# Sch_Quick_Dev_R2.net
KiCad netlist of a schematic drawn in EasyEDA
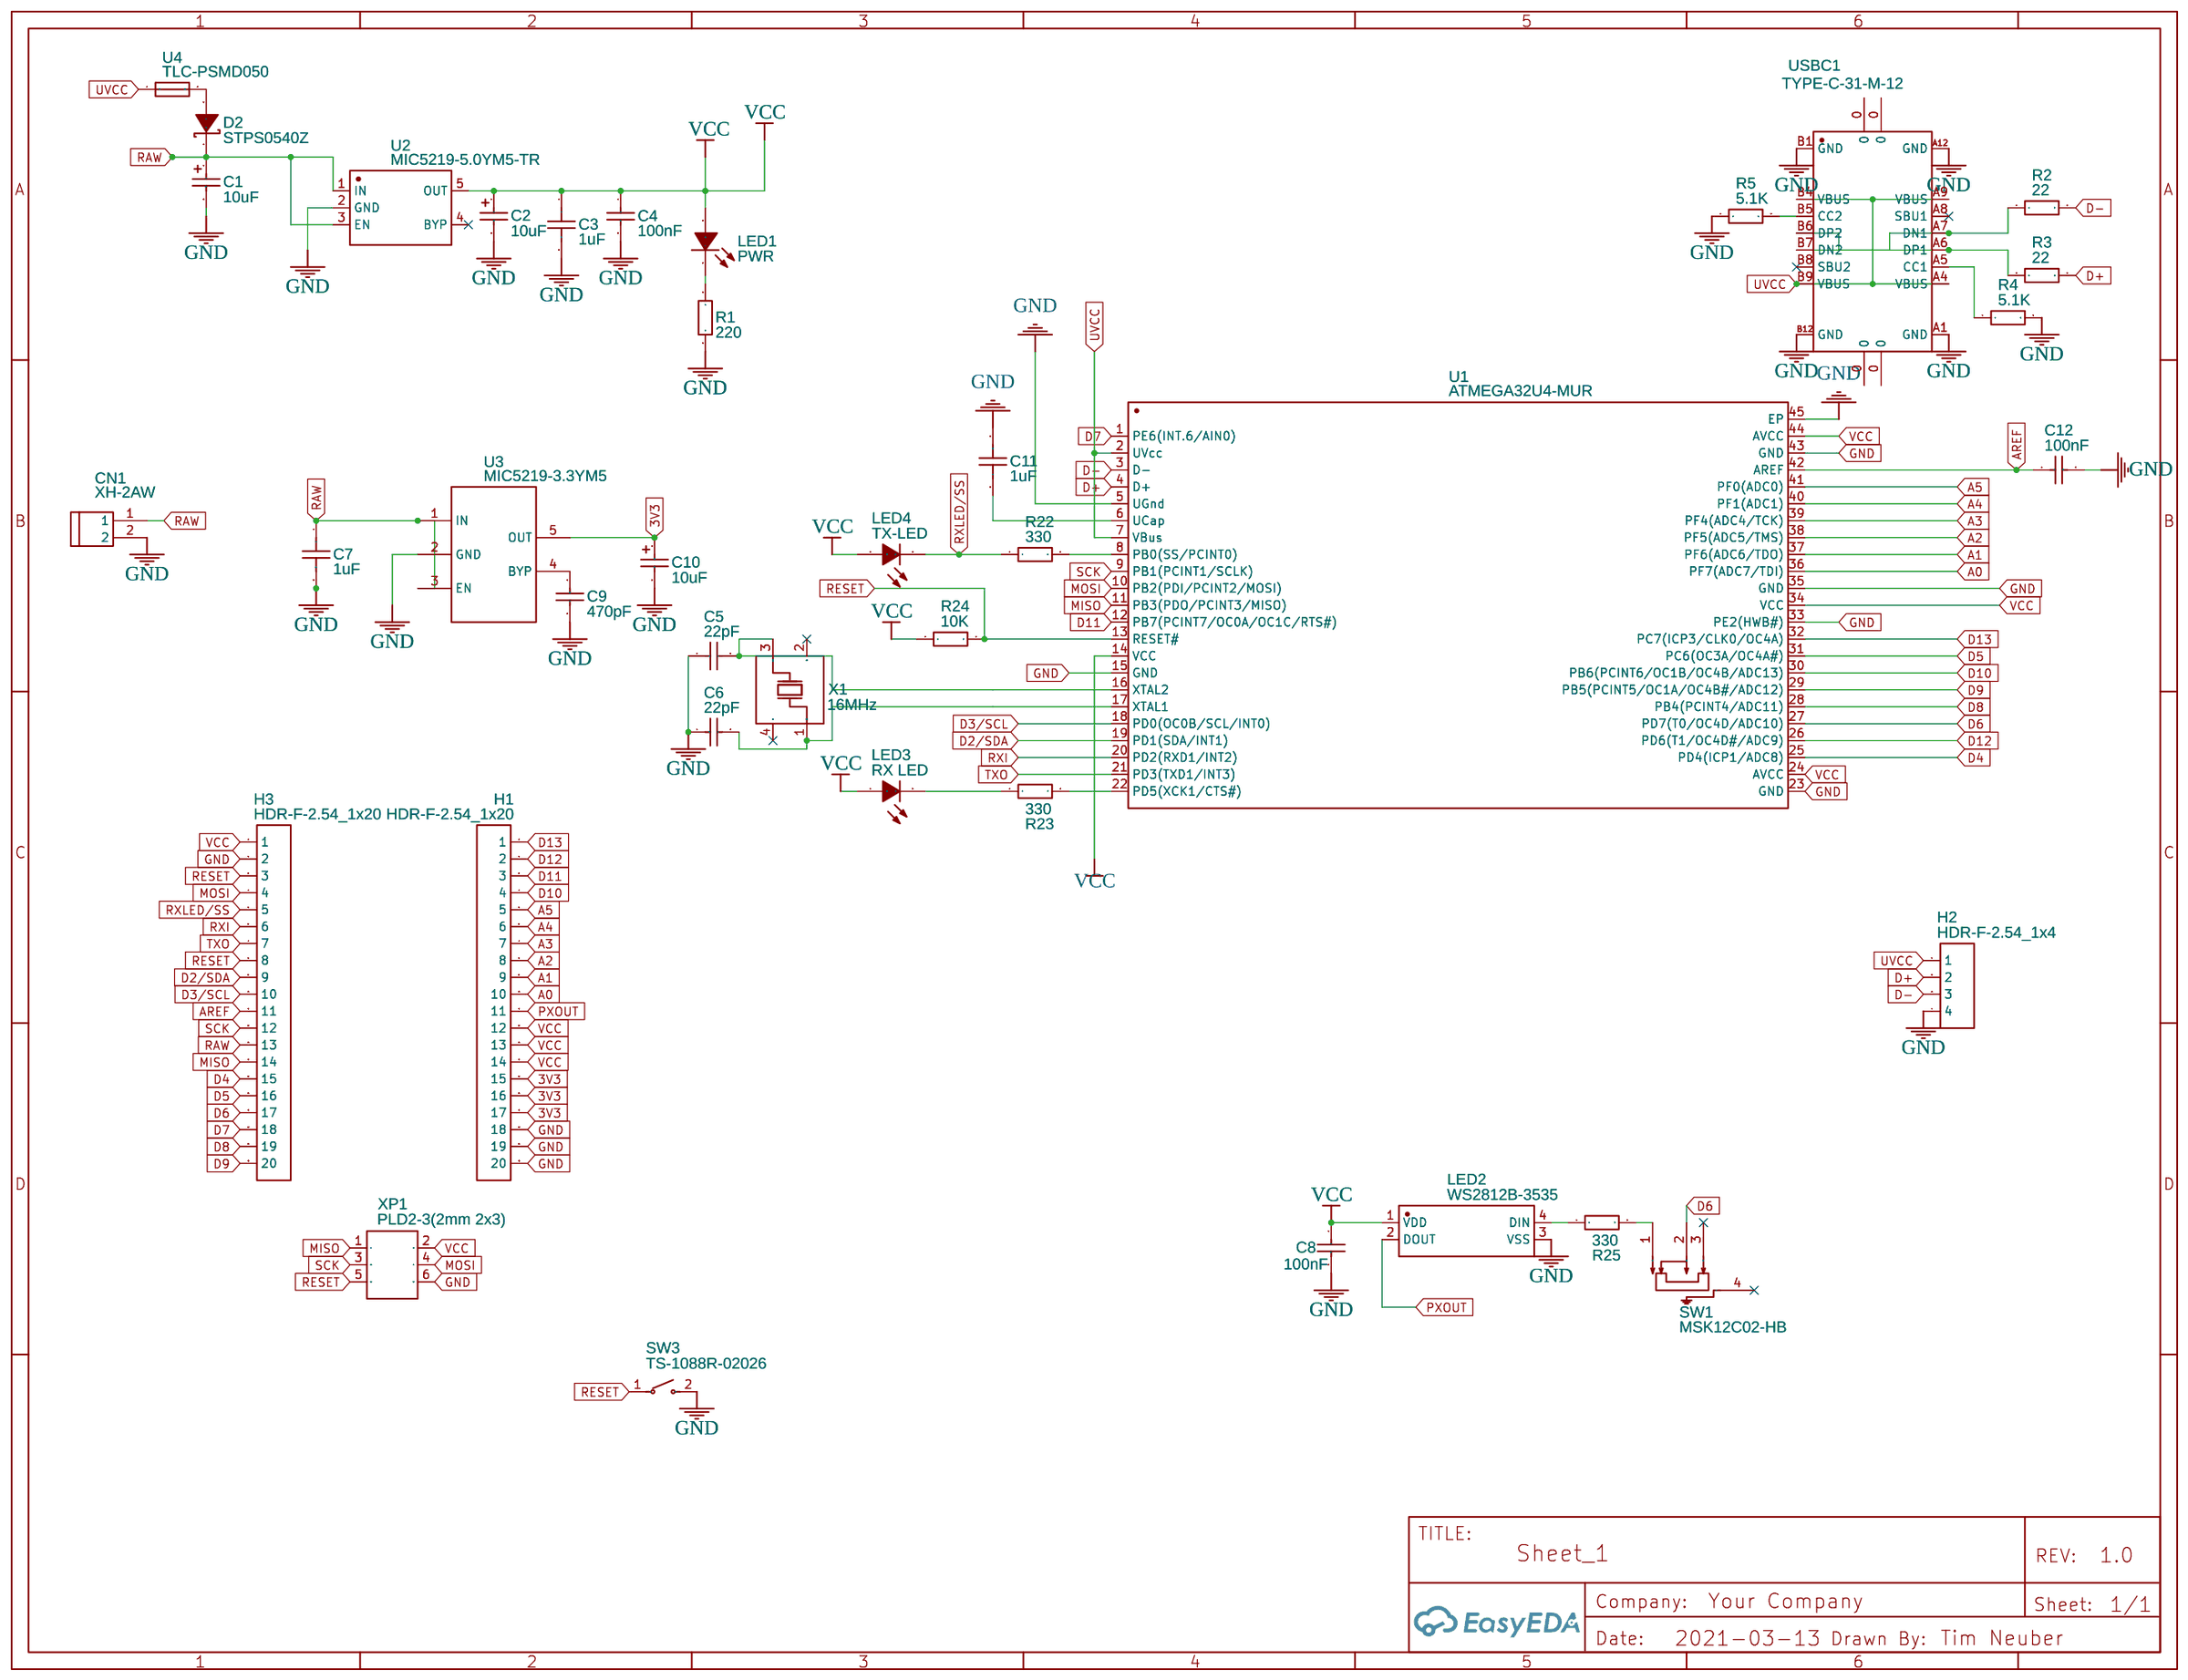
[diagram p0: schematic sheet]

(export (version "E")
  (design (tool "Eeschema 10.0.6"))
  (components
    (comp (ref "C1")
      (value "10uF")
      (fields
        (field (name "BOM_Manufacturer Part") "TAJA106K016RNJ")
        (field (name "BOM_Supplier Part") "C7171")
      )
      (libsource (lib "") (part "TAJA106K016RNJ"))
    )
    (comp (ref "C2")
      (value "10uF")
      (fields
        (field (name "BOM_Manufacturer Part") "TAJA106K016RNJ")
        (field (name "BOM_Supplier Part") "C7171")
      )
      (libsource (lib "") (part "TAJA106K016RNJ"))
    )
    (comp (ref "C3")
      (value "1uF")
      (fields
        (field (name "BOM_Manufacturer Part") "CL05A105KA5NQNC")
        (field (name "BOM_Supplier Part") "C52923")
      )
      (libsource (lib "") (part "CL05A105KA5NQNC"))
    )
    (comp (ref "C4")
      (value "100nF")
      (fields
        (field (name "BOM_Manufacturer Part") "CL05B104KO5NNNC")
        (field (name "BOM_Supplier Part") "C1525")
      )
      (libsource (lib "") (part "CL05B104KO5NNNC"))
    )
    (comp (ref "C5")
      (value "22pF")
      (fields
        (field (name "BOM_Manufacturer Part") "0402CG220J500NT")
        (field (name "BOM_Supplier Part") "C1555")
      )
      (libsource (lib "") (part "0402CG220J500NT"))
    )
    (comp (ref "C6")
      (value "22pF")
      (fields
        (field (name "BOM_Manufacturer Part") "0402CG220J500NT")
        (field (name "BOM_Supplier Part") "C1555")
      )
      (libsource (lib "") (part "0402CG220J500NT"))
    )
    (comp (ref "C7")
      (value "1uF")
      (fields
        (field (name "BOM_Manufacturer Part") "CL05A105KA5NQNC")
        (field (name "BOM_Supplier Part") "C52923")
      )
      (libsource (lib "") (part "CL05A105KA5NQNC"))
    )
    (comp (ref "C8")
      (value "100nF")
      (fields
        (field (name "BOM_Manufacturer Part") "CL05B104KO5NNNC")
        (field (name "BOM_Supplier Part") "C1525")
      )
      (libsource (lib "") (part "CL05B104KO5NNNC"))
    )
    (comp (ref "C9")
      (value "470pF")
      (fields
        (field (name "BOM_Manufacturer Part") "0402B471K500NT")
        (field (name "BOM_Supplier Part") "C1537")
      )
      (libsource (lib "") (part "0402B471K500NT"))
    )
    (comp (ref "C10")
      (value "10uF")
      (fields
        (field (name "BOM_Manufacturer Part") "TAJA106K016RNJ")
        (field (name "BOM_Supplier Part") "C7171")
      )
      (libsource (lib "") (part "TAJA106K016RNJ"))
    )
    (comp (ref "C11")
      (value "1uF")
      (fields
        (field (name "BOM_Manufacturer Part") "CL05A105KA5NQNC")
        (field (name "BOM_Supplier Part") "C52923")
      )
      (libsource (lib "") (part "CL05A105KA5NQNC"))
    )
    (comp (ref "C12")
      (value "100nF")
      (fields
        (field (name "BOM_Manufacturer Part") "CL05B104KO5NNNC")
        (field (name "BOM_Supplier Part") "C1525")
      )
      (libsource (lib "") (part "CL05B104KO5NNNC_1"))
    )
    (comp (ref "CN1")
      (value "XH-2AW")
      (fields (field (name "BOM_Supplier Part") "C33132"))
      (libsource (lib "") (part "XH-2AW"))
    )
    (comp (ref "D2")
      (value "STPS0540Z")
      (fields (field (name "BOM_Supplier Part") "C181835"))
      (libsource (lib "") (part "STPS0540Z"))
    )
    (comp (ref "H1")
      (value "HDR-F-2.54_1x20")
      (fields (field (name "BOM_Supplier Part") "C50984"))
      (libsource (lib "") (part "HDR-F-2.54_1x20_1"))
    )
    (comp (ref "H2")
      (value "HDR-F-2.54_1x4")
      (fields (field (name "BOM_Supplier Part") "C225501"))
      (libsource (lib "") (part "HDR-F-2.54_1x4"))
    )
    (comp (ref "H3")
      (value "HDR-F-2.54_1x20")
      (fields (field (name "BOM_Supplier Part") "C50984"))
      (libsource (lib "") (part "HDR-F-2.54_1x20"))
    )
    (comp (ref "LED1")
      (value "PWR")
      (fields (field (name "BOM_Manufacturer Part") "KT-0603R") (field (name "BOM_Supplier Part") "C2286"))
      (libsource (lib "") (part "KT-0603R"))
    )
    (comp (ref "LED2")
      (value "WS2812B-3535")
      (fields (field (name "BOM_Supplier Part") "C114583"))
      (libsource (lib "") (part "WS2812B-3535"))
    )
    (comp (ref "LED3")
      (value "RX LED")
      (fields
        (field (name "BOM_Manufacturer Part") "19-217/BHC-ZL1M2RY/3T")
        (field (name "BOM_Supplier Part") "C72041")
      )
      (libsource (lib "") (part "19-217/BHC-ZL1M2RY/3T"))
    )
    (comp (ref "LED4")
      (value "TX-LED")
      (fields
        (field (name "BOM_Manufacturer Part") "19-217/BHC-ZL1M2RY/3T")
        (field (name "BOM_Supplier Part") "C72041")
      )
      (libsource (lib "") (part "19-217/BHC-ZL1M2RY/3T"))
    )
    (comp (ref "R1")
      (value "220")
      (fields
        (field (name "BOM_Manufacturer Part") "0603WAF2200T5E")
        (field (name "BOM_Supplier Part") "C22962")
      )
      (libsource (lib "") (part "0603WAF2200T5E"))
    )
    (comp (ref "R2")
      (value "22")
      (fields
        (field (name "BOM_Manufacturer Part") "0402WGF220JTCE")
        (field (name "BOM_Supplier Part") "C25092")
      )
      (libsource (lib "") (part "0402WGF220JTCE"))
    )
    (comp (ref "R3")
      (value "22")
      (fields
        (field (name "BOM_Manufacturer Part") "0402WGF220JTCE")
        (field (name "BOM_Supplier Part") "C25092")
      )
      (libsource (lib "") (part "0402WGF220JTCE"))
    )
    (comp (ref "R4")
      (value "5.1K")
      (fields
        (field (name "BOM_Manufacturer Part") "0402WGF5101TCE")
        (field (name "BOM_Supplier Part") "C25905")
      )
      (libsource (lib "") (part "0402WGF5101TCE"))
    )
    (comp (ref "R5")
      (value "5.1K")
      (fields
        (field (name "BOM_Manufacturer Part") "0402WGF5101TCE")
        (field (name "BOM_Supplier Part") "C25905")
      )
      (libsource (lib "") (part "0402WGF5101TCE"))
    )
    (comp (ref "R22")
      (value "330")
      (fields
        (field (name "BOM_Manufacturer Part") "0402WGF3300TCE")
        (field (name "BOM_Supplier Part") "C25104")
      )
      (libsource (lib "") (part "0402WGF3300TCE"))
    )
    (comp (ref "R23")
      (value "330")
      (fields
        (field (name "BOM_Manufacturer Part") "0402WGF3300TCE")
        (field (name "BOM_Supplier Part") "C25104")
      )
      (libsource (lib "") (part "0402WGF3300TCE"))
    )
    (comp (ref "R24")
      (value "10K")
      (fields
        (field (name "BOM_Manufacturer Part") "0402WGF1002TCE")
        (field (name "BOM_Supplier Part") "C25744")
      )
      (libsource (lib "") (part "0402WGF1002TCE"))
    )
    (comp (ref "R25")
      (value "330")
      (fields
        (field (name "BOM_Manufacturer Part") "0402WGF3300TCE")
        (field (name "BOM_Supplier Part") "C25104")
      )
      (libsource (lib "") (part "0402WGF3300TCE"))
    )
    (comp (ref "SW1")
      (value "MSK12C02-HB")
      (fields (field (name "BOM_Supplier Part") "C431541"))
      (libsource (lib "") (part "MSK12C02-HB"))
    )
    (comp (ref "SW3")
      (value "TS-1088R-02026")
      (fields (field (name "BOM_Supplier Part") "C455280"))
      (libsource (lib "") (part "TS-1088R-02026"))
    )
    (comp (ref "U1")
      (value "ATMEGA32U4-MUR")
      (fields (field (name "BOM_Supplier Part") "C45874"))
      (libsource (lib "") (part "ATMEGA32U4-MUR"))
    )
    (comp (ref "U2")
      (value "MIC5219-5.0YM5-TR")
      (fields (field (name "BOM_Supplier Part") "C144182"))
      (libsource (lib "") (part "MIC5219-5.0YM5-TR"))
    )
    (comp (ref "U3")
      (value "MIC5219-3.3YM5")
      (fields (field (name "BOM_Supplier Part") "C29613"))
      (libsource (lib "") (part "MIC5219-3.3YM5"))
    )
    (comp (ref "U4")
      (value "TLC-PSMD050")
      (fields (field (name "BOM_Supplier Part") "C261942"))
      (libsource (lib "") (part "TLC-PSMD050"))
    )
    (comp (ref "USBC1")
      (value "TYPE-C-31-M-12")
      (fields (field (name "BOM_Supplier Part") "C165948"))
      (libsource (lib "") (part "TYPE-C-31-M-12"))
    )
    (comp (ref "X1")
      (value "16MHz")
      (fields
        (field (name "BOM_Manufacturer Part") "X322516MLB4SI")
        (field (name "BOM_Supplier Part") "C13738")
      )
      (libsource (lib "") (part "X322516MLB4SI"))
    )
    (comp (ref "XP1")
      (value "PLD2-3(2mm 2x3)")
      (fields (field (name "BOM_Manufacturer Part") "PLD-3 2,54 2x3"))
      (libsource (lib "") (part "PLD2-3(2mm 2x3)"))
    )
  )
  (nets
    (net (code "1") (name "3V3") (class "Default")
      (node (ref "C10") (pin "1") (pinfunction "1_1") (pintype "input"))
      (node (ref "H1") (pin "15") (pinfunction "15_15") (pintype "unspecified"))
      (node (ref "H1") (pin "16") (pinfunction "16_16") (pintype "unspecified"))
      (node (ref "H1") (pin "17") (pinfunction "17_17") (pintype "unspecified"))
      (node (ref "U3") (pin "5") (pinfunction "OUT_5") (pintype "unspecified"))
    )
    (net (code "2") (name "A0") (class "Default")
      (node (ref "H1") (pin "10") (pinfunction "10_10") (pintype "unspecified"))
      (node (ref "U1") (pin "36") (pinfunction "PF7(ADC7/TDI)_36") (pintype "unspecified"))
    )
    (net (code "3") (name "A1") (class "Default")
      (node (ref "H1") (pin "9") (pinfunction "9_9") (pintype "unspecified"))
      (node (ref "U1") (pin "37") (pinfunction "PF6(ADC6/TDO)_37") (pintype "unspecified"))
    )
    (net (code "4") (name "A2") (class "Default")
      (node (ref "H1") (pin "8") (pinfunction "8_8") (pintype "unspecified"))
      (node (ref "U1") (pin "38") (pinfunction "PF5(ADC5/TMS)_38") (pintype "unspecified"))
    )
    (net (code "5") (name "A3") (class "Default")
      (node (ref "H1") (pin "7") (pinfunction "7_7") (pintype "unspecified"))
      (node (ref "U1") (pin "39") (pinfunction "PF4(ADC4/TCK)_39") (pintype "unspecified"))
    )
    (net (code "6") (name "A4") (class "Default")
      (node (ref "H1") (pin "6") (pinfunction "6_6") (pintype "unspecified"))
      (node (ref "U1") (pin "40") (pinfunction "PF1(ADC1)_40") (pintype "unspecified"))
    )
    (net (code "7") (name "A5") (class "Default")
      (node (ref "H1") (pin "5") (pinfunction "5_5") (pintype "unspecified"))
      (node (ref "U1") (pin "41") (pinfunction "PF0(ADC0)_41") (pintype "unspecified"))
    )
    (net (code "8") (name "AREF") (class "Default")
      (node (ref "C12") (pin "1") (pinfunction "1_1") (pintype "input"))
      (node (ref "H3") (pin "11") (pinfunction "11_11") (pintype "unspecified"))
      (node (ref "U1") (pin "42") (pinfunction "AREF_42") (pintype "unspecified"))
    )
    (net (code "9") (name "D+") (class "Default")
      (node (ref "H2") (pin "2") (pinfunction "2_2") (pintype "unspecified"))
      (node (ref "R3") (pin "2") (pinfunction "2_2") (pintype "input"))
      (node (ref "U1") (pin "4") (pinfunction "D+_4") (pintype "unspecified"))
    )
    (net (code "10") (name "D-") (class "Default")
      (node (ref "H2") (pin "3") (pinfunction "3_3") (pintype "unspecified"))
      (node (ref "R2") (pin "2") (pinfunction "2_2") (pintype "input"))
      (node (ref "U1") (pin "3") (pinfunction "D-_3") (pintype "unspecified"))
    )
    (net (code "11") (name "D2{slash}SDA") (class "Default")
      (node (ref "H3") (pin "9") (pinfunction "9_9") (pintype "unspecified"))
      (node (ref "U1") (pin "19") (pinfunction "PD1(SDA/INT1)_19") (pintype "unspecified"))
    )
    (net (code "12") (name "D3{slash}SCL") (class "Default")
      (node (ref "H3") (pin "10") (pinfunction "10_10") (pintype "unspecified"))
      (node (ref "U1") (pin "18") (pinfunction "PD0(OC0B/SCL/INT0)_18") (pintype "unspecified"))
    )
    (net (code "13") (name "D4") (class "Default")
      (node (ref "H3") (pin "15") (pinfunction "15_15") (pintype "unspecified"))
      (node (ref "U1") (pin "25") (pinfunction "PD4(ICP1/ADC8)_25") (pintype "unspecified"))
    )
    (net (code "14") (name "D5") (class "Default")
      (node (ref "H3") (pin "16") (pinfunction "16_16") (pintype "unspecified"))
      (node (ref "U1") (pin "31") (pinfunction "PC6(OC3A/OC4A#)_31") (pintype "unspecified"))
    )
    (net (code "15") (name "D6") (class "Default")
      (node (ref "H3") (pin "17") (pinfunction "17_17") (pintype "unspecified"))
      (node (ref "SW1") (pin "2") (pinfunction "2_2") (pintype "unspecified"))
      (node (ref "U1") (pin "27") (pinfunction "PD7(T0/OC4D/ADC10)_27") (pintype "unspecified"))
    )
    (net (code "16") (name "D7") (class "Default")
      (node (ref "H3") (pin "18") (pinfunction "18_18") (pintype "unspecified"))
      (node (ref "U1") (pin "1") (pinfunction "PE6(INT.6/AIN0)_1") (pintype "unspecified"))
    )
    (net (code "17") (name "D8") (class "Default")
      (node (ref "H3") (pin "19") (pinfunction "19_19") (pintype "unspecified"))
      (node (ref "U1") (pin "28") (pinfunction "PB4(PCINT4/ADC11)_28") (pintype "unspecified"))
    )
    (net (code "18") (name "D9") (class "Default")
      (node (ref "H3") (pin "20") (pinfunction "20_20") (pintype "unspecified"))
      (node (ref "U1") (pin "29") (pinfunction "PB5(PCINT5/OC1A/OC4B#/ADC12)_29") (pintype "unspecified"))
    )
    (net (code "19") (name "D10") (class "Default")
      (node (ref "H1") (pin "4") (pinfunction "4_4") (pintype "unspecified"))
      (node (ref "U1") (pin "30") (pinfunction "PB6(PCINT6/OC1B/OC4B/ADC13)_30") (pintype "unspecified"))
    )
    (net (code "20") (name "D11") (class "Default")
      (node (ref "H1") (pin "3") (pinfunction "3_3") (pintype "unspecified"))
      (node (ref "U1") (pin "12") (pinfunction "PB7(PCINT7/OC0A/OC1C/RTS#)_12") (pintype "unspecified"))
    )
    (net (code "21") (name "D12") (class "Default")
      (node (ref "H1") (pin "2") (pinfunction "2_2") (pintype "unspecified"))
      (node (ref "U1") (pin "26") (pinfunction "PD6(T1/OC4D#/ADC9)_26") (pintype "unspecified"))
    )
    (net (code "22") (name "D13") (class "Default")
      (node (ref "H1") (pin "1") (pinfunction "1_1") (pintype "unspecified"))
      (node (ref "U1") (pin "32") (pinfunction "PC7(ICP3/CLK0/OC4A)_32") (pintype "unspecified"))
    )
    (net (code "23") (name "GND") (class "Default")
      (node (ref "C1") (pin "2") (pinfunction "2_2") (pintype "input"))
      (node (ref "C10") (pin "2") (pinfunction "2_2") (pintype "input"))
      (node (ref "C11") (pin "1") (pinfunction "1_1") (pintype "unspecified"))
      (node (ref "C12") (pin "2") (pinfunction "2_2") (pintype "input"))
      (node (ref "C2") (pin "2") (pinfunction "2_2") (pintype "input"))
      (node (ref "C3") (pin "2") (pinfunction "2_2") (pintype "unspecified"))
      (node (ref "C4") (pin "2") (pinfunction "2_2") (pintype "input"))
      (node (ref "C5") (pin "1") (pinfunction "1_1") (pintype "input"))
      (node (ref "C6") (pin "1") (pinfunction "1_1") (pintype "input"))
      (node (ref "C7") (pin "2") (pinfunction "2_2") (pintype "unspecified"))
      (node (ref "C8") (pin "2") (pinfunction "2_2") (pintype "input"))
      (node (ref "C9") (pin "1") (pinfunction "1_1") (pintype "input"))
      (node (ref "CN1") (pin "2") (pinfunction "2_2") (pintype "unspecified"))
      (node (ref "H1") (pin "18") (pinfunction "18_18") (pintype "unspecified"))
      (node (ref "H1") (pin "19") (pinfunction "19_19") (pintype "unspecified"))
      (node (ref "H1") (pin "20") (pinfunction "20_20") (pintype "unspecified"))
      (node (ref "H2") (pin "4") (pinfunction "4_4") (pintype "unspecified"))
      (node (ref "H3") (pin "2") (pinfunction "2_2") (pintype "unspecified"))
      (node (ref "LED2") (pin "3") (pinfunction "VSS_3") (pintype "unspecified"))
      (node (ref "R1") (pin "1") (pinfunction "1_1") (pintype "input"))
      (node (ref "R4") (pin "2") (pinfunction "2_2") (pintype "input"))
      (node (ref "R5") (pin "1") (pinfunction "1_1") (pintype "input"))
      (node (ref "SW3") (pin "2") (pinfunction "2_2") (pintype "unspecified"))
      (node (ref "U1") (pin "15") (pinfunction "GND_15") (pintype "unspecified"))
      (node (ref "U1") (pin "23") (pinfunction "GND_23") (pintype "unspecified"))
      (node (ref "U1") (pin "33") (pinfunction "PE2(HWB#)_33") (pintype "unspecified"))
      (node (ref "U1") (pin "35") (pinfunction "GND_35") (pintype "unspecified"))
      (node (ref "U1") (pin "43") (pinfunction "GND_43") (pintype "unspecified"))
      (node (ref "U1") (pin "45") (pinfunction "EP_45") (pintype "unspecified"))
      (node (ref "U1") (pin "5") (pinfunction "UGnd_5") (pintype "unspecified"))
      (node (ref "U2") (pin "2") (pinfunction "GND_2") (pintype "unspecified"))
      (node (ref "U3") (pin "2") (pinfunction "GND_2") (pintype "unspecified"))
      (node (ref "USBC1") (pin "A1") (pinfunction "GND_A1") (pintype "unspecified"))
      (node (ref "USBC1") (pin "A12") (pinfunction "GND_A12") (pintype "unspecified"))
      (node (ref "USBC1") (pin "B1") (pinfunction "GND_B1") (pintype "unspecified"))
      (node (ref "USBC1") (pin "B12") (pinfunction "GND_B12") (pintype "unspecified"))
      (node (ref "XP1") (pin "6") (pinfunction "6_6") (pintype "unspecified"))
    )
    (net (code "24") (name "MISO") (class "Default")
      (node (ref "H3") (pin "14") (pinfunction "14_14") (pintype "unspecified"))
      (node (ref "U1") (pin "11") (pinfunction "PB3(PDO/PCINT3/MISO)_11") (pintype "unspecified"))
      (node (ref "XP1") (pin "1") (pinfunction "1_1") (pintype "unspecified"))
    )
    (net (code "25") (name "MOSI") (class "Default")
      (node (ref "H3") (pin "4") (pinfunction "4_4") (pintype "unspecified"))
      (node (ref "U1") (pin "10") (pinfunction "PB2(PDI/PCINT2/MOSI)_10") (pintype "unspecified"))
      (node (ref "XP1") (pin "4") (pinfunction "4_4") (pintype "unspecified"))
    )
    (net (code "26") (name "Net-(D2-A)") (class "Default")
      (node (ref "D2") (pin "2") (pinfunction "A_2") (pintype "unspecified"))
      (node (ref "U4") (pin "2") (pinfunction "2_2") (pintype "unspecified"))
    )
    (net (code "27") (name "Net-(LED1-K)") (class "Default")
      (node (ref "LED1") (pin "2") (pinfunction "K_2") (pintype "unspecified"))
      (node (ref "R1") (pin "2") (pinfunction "2_2") (pintype "input"))
    )
    (net (code "28") (name "Net-(LED2-DIN)") (class "Default")
      (node (ref "LED2") (pin "4") (pinfunction "DIN_4") (pintype "unspecified"))
      (node (ref "R25") (pin "1") (pinfunction "1_1") (pintype "input"))
    )
    (net (code "29") (name "Net-(LED3-C)") (class "Default")
      (node (ref "LED3") (pin "2") (pinfunction "C_2") (pintype "input"))
      (node (ref "R23") (pin "1") (pinfunction "1_1") (pintype "input"))
    )
    (net (code "30") (name "Net-(R25-Pad2)") (class "Default")
      (node (ref "R25") (pin "2") (pinfunction "2_2") (pintype "input"))
      (node (ref "SW1") (pin "1") (pinfunction "1_1") (pintype "unspecified"))
    )
    (net (code "31") (name "Net-(U1-PB0(SS{slash}PCINT0))") (class "Default")
      (node (ref "R22") (pin "2") (pinfunction "2_2") (pintype "input"))
      (node (ref "U1") (pin "8") (pinfunction "PB0(SS/PCINT0)_8") (pintype "unspecified"))
    )
    (net (code "32") (name "Net-(U1-PD5(XCK1{slash}CTS#))") (class "Default")
      (node (ref "R23") (pin "2") (pinfunction "2_2") (pintype "input"))
      (node (ref "U1") (pin "22") (pinfunction "PD5(XCK1/CTS#)_22") (pintype "unspecified"))
    )
    (net (code "33") (name "Net-(U1-UCap)") (class "Default")
      (node (ref "C11") (pin "2") (pinfunction "2_2") (pintype "unspecified"))
      (node (ref "U1") (pin "6") (pinfunction "UCap_6") (pintype "unspecified"))
    )
    (net (code "34") (name "Net-(U1-XTAL1)") (class "Default")
      (node (ref "C6") (pin "2") (pinfunction "2_2") (pintype "input"))
      (node (ref "U1") (pin "17") (pinfunction "XTAL1_17") (pintype "unspecified"))
      (node (ref "X1") (pin "1") (pinfunction "OSC1_1") (pintype "unspecified"))
    )
    (net (code "35") (name "Net-(U1-XTAL2)") (class "Default")
      (node (ref "C5") (pin "2") (pinfunction "2_2") (pintype "input"))
      (node (ref "U1") (pin "16") (pinfunction "XTAL2_16") (pintype "unspecified"))
      (node (ref "X1") (pin "3") (pinfunction "OSC2_3") (pintype "unspecified"))
    )
    (net (code "36") (name "Net-(U3-BYP)") (class "Default")
      (node (ref "C9") (pin "2") (pinfunction "2_2") (pintype "input"))
      (node (ref "U3") (pin "4") (pinfunction "BYP_4") (pintype "unspecified"))
    )
    (net (code "37") (name "Net-(USBC1-CC1)") (class "Default")
      (node (ref "R4") (pin "1") (pinfunction "1_1") (pintype "input"))
      (node (ref "USBC1") (pin "A5") (pinfunction "CC1_A5") (pintype "unspecified"))
    )
    (net (code "38") (name "Net-(USBC1-CC2)") (class "Default")
      (node (ref "R5") (pin "2") (pinfunction "2_2") (pintype "input"))
      (node (ref "USBC1") (pin "B5") (pinfunction "CC2_B5") (pintype "unspecified"))
    )
    (net (code "39") (name "Net-(USBC1-DN1)") (class "Default")
      (node (ref "R2") (pin "1") (pinfunction "1_1") (pintype "input"))
      (node (ref "USBC1") (pin "A7") (pinfunction "DN1_A7") (pintype "unspecified"))
      (node (ref "USBC1") (pin "B7") (pinfunction "DN2_B7") (pintype "unspecified"))
    )
    (net (code "40") (name "Net-(USBC1-DP1)") (class "Default")
      (node (ref "R3") (pin "1") (pinfunction "1_1") (pintype "input"))
      (node (ref "USBC1") (pin "A6") (pinfunction "DP1_A6") (pintype "unspecified"))
      (node (ref "USBC1") (pin "B6") (pinfunction "DP2_B6") (pintype "unspecified"))
    )
    (net (code "41") (name "PXOUT") (class "Default")
      (node (ref "H1") (pin "11") (pinfunction "11_11") (pintype "unspecified"))
      (node (ref "LED2") (pin "2") (pinfunction "DOUT_2") (pintype "unspecified"))
    )
    (net (code "42") (name "RAW") (class "Default")
      (node (ref "C1") (pin "1") (pinfunction "1_1") (pintype "input"))
      (node (ref "C7") (pin "1") (pinfunction "1_1") (pintype "unspecified"))
      (node (ref "CN1") (pin "1") (pinfunction "1_1") (pintype "unspecified"))
      (node (ref "D2") (pin "1") (pinfunction "K_1") (pintype "unspecified"))
      (node (ref "H3") (pin "13") (pinfunction "13_13") (pintype "unspecified"))
      (node (ref "U2") (pin "1") (pinfunction "IN_1") (pintype "unspecified"))
      (node (ref "U2") (pin "3") (pinfunction "EN_3") (pintype "unspecified"))
      (node (ref "U3") (pin "1") (pinfunction "IN_1") (pintype "unspecified"))
      (node (ref "U3") (pin "3") (pinfunction "EN_3") (pintype "unspecified"))
    )
    (net (code "43") (name "RESET") (class "Default")
      (node (ref "H3") (pin "3") (pinfunction "3_3") (pintype "unspecified"))
      (node (ref "H3") (pin "8") (pinfunction "8_8") (pintype "unspecified"))
      (node (ref "R24") (pin "2") (pinfunction "2_2") (pintype "input"))
      (node (ref "SW3") (pin "1") (pinfunction "1_1") (pintype "unspecified"))
      (node (ref "U1") (pin "13") (pinfunction "RESET#_13") (pintype "unspecified"))
      (node (ref "XP1") (pin "5") (pinfunction "5_5") (pintype "unspecified"))
    )
    (net (code "44") (name "RXI") (class "Default")
      (node (ref "H3") (pin "6") (pinfunction "6_6") (pintype "unspecified"))
      (node (ref "U1") (pin "20") (pinfunction "PD2(RXD1/INT2)_20") (pintype "unspecified"))
    )
    (net (code "45") (name "RXLED{slash}SS") (class "Default")
      (node (ref "H3") (pin "5") (pinfunction "5_5") (pintype "unspecified"))
      (node (ref "LED4") (pin "2") (pinfunction "C_2") (pintype "input"))
      (node (ref "R22") (pin "1") (pinfunction "1_1") (pintype "input"))
    )
    (net (code "46") (name "SCK") (class "Default")
      (node (ref "H3") (pin "12") (pinfunction "12_12") (pintype "unspecified"))
      (node (ref "U1") (pin "9") (pinfunction "PB1(PCINT1/SCLK)_9") (pintype "unspecified"))
      (node (ref "XP1") (pin "3") (pinfunction "3_3") (pintype "unspecified"))
    )
    (net (code "47") (name "TXO") (class "Default")
      (node (ref "H3") (pin "7") (pinfunction "7_7") (pintype "unspecified"))
      (node (ref "U1") (pin "21") (pinfunction "PD3(TXD1/INT3)_21") (pintype "unspecified"))
    )
    (net (code "48") (name "UVCC") (class "Default")
      (node (ref "H2") (pin "1") (pinfunction "1_1") (pintype "unspecified"))
      (node (ref "U1") (pin "2") (pinfunction "UVcc_2") (pintype "unspecified"))
      (node (ref "U1") (pin "7") (pinfunction "VBus_7") (pintype "unspecified"))
      (node (ref "U4") (pin "1") (pinfunction "1_1") (pintype "unspecified"))
      (node (ref "USBC1") (pin "A4") (pinfunction "VBUS_A4") (pintype "unspecified"))
      (node (ref "USBC1") (pin "A9") (pinfunction "VBUS_A9") (pintype "unspecified"))
      (node (ref "USBC1") (pin "B4") (pinfunction "VBUS_B4") (pintype "unspecified"))
      (node (ref "USBC1") (pin "B9") (pinfunction "VBUS_B9") (pintype "unspecified"))
    )
    (net (code "49") (name "VCC") (class "Default")
      (node (ref "C2") (pin "1") (pinfunction "1_1") (pintype "input"))
      (node (ref "C3") (pin "1") (pinfunction "1_1") (pintype "unspecified"))
      (node (ref "C4") (pin "1") (pinfunction "1_1") (pintype "input"))
      (node (ref "C8") (pin "1") (pinfunction "1_1") (pintype "input"))
      (node (ref "H1") (pin "12") (pinfunction "12_12") (pintype "unspecified"))
      (node (ref "H1") (pin "13") (pinfunction "13_13") (pintype "unspecified"))
      (node (ref "H1") (pin "14") (pinfunction "14_14") (pintype "unspecified"))
      (node (ref "H3") (pin "1") (pinfunction "1_1") (pintype "unspecified"))
      (node (ref "LED1") (pin "1") (pinfunction "A_1") (pintype "unspecified"))
      (node (ref "LED2") (pin "1") (pinfunction "VDD_1") (pintype "unspecified"))
      (node (ref "LED3") (pin "1") (pinfunction "A_1") (pintype "input"))
      (node (ref "LED4") (pin "1") (pinfunction "A_1") (pintype "input"))
      (node (ref "R24") (pin "1") (pinfunction "1_1") (pintype "input"))
      (node (ref "U1") (pin "14") (pinfunction "VCC_14") (pintype "unspecified"))
      (node (ref "U1") (pin "24") (pinfunction "AVCC_24") (pintype "unspecified"))
      (node (ref "U1") (pin "34") (pinfunction "VCC_34") (pintype "unspecified"))
      (node (ref "U1") (pin "44") (pinfunction "AVCC_44") (pintype "unspecified"))
      (node (ref "U2") (pin "5") (pinfunction "OUT_5") (pintype "unspecified"))
      (node (ref "XP1") (pin "2") (pinfunction "2_2") (pintype "unspecified"))
    )
    (net (code "50") (name "unconnected-(SW1-Pad3)") (class "Default")
      (node (ref "SW1") (pin "3") (pinfunction "3_3") (pintype "unspecified+no_connect"))
    )
    (net (code "51") (name "unconnected-(SW1-Pad4)") (class "Default")
      (node (ref "SW1") (pin "4") (pinfunction "4_4") (pintype "unspecified+no_connect"))
    )
    (net (code "52") (name "unconnected-(U2-BYP-Pad4)") (class "Default")
      (node (ref "U2") (pin "4") (pinfunction "BYP_4") (pintype "unspecified+no_connect"))
    )
    (net (code "53") (name "unconnected-(USBC1-Pad0)") (class "Default")
      (node (ref "USBC1") (pin "0") (pinfunction "0_0") (pintype "unspecified"))
    )
    (net (code "54") (name "unconnected-(USBC1-Pad0)_1") (class "Default")
      (node (ref "USBC1") (pin "0") (pinfunction "0_0") (pintype "unspecified"))
    )
    (net (code "55") (name "unconnected-(USBC1-Pad0)_2") (class "Default")
      (node (ref "USBC1") (pin "0") (pinfunction "0_0") (pintype "unspecified"))
    )
    (net (code "56") (name "unconnected-(USBC1-Pad0)_3") (class "Default")
      (node (ref "USBC1") (pin "0") (pinfunction "0_0") (pintype "unspecified"))
    )
    (net (code "57") (name "unconnected-(USBC1-SBU1-PadA8)") (class "Default")
      (node (ref "USBC1") (pin "A8") (pinfunction "SBU1_A8") (pintype "unspecified+no_connect"))
    )
    (net (code "58") (name "unconnected-(USBC1-SBU2-PadB8)") (class "Default")
      (node (ref "USBC1") (pin "B8") (pinfunction "SBU2_B8") (pintype "unspecified+no_connect"))
    )
    (net (code "59") (name "unconnected-(X1-GND-Pad2)") (class "Default")
      (node (ref "X1") (pin "2") (pinfunction "GND_2") (pintype "unspecified+no_connect"))
    )
    (net (code "60") (name "unconnected-(X1-GND-Pad4)") (class "Default")
      (node (ref "X1") (pin "4") (pinfunction "GND_4") (pintype "unspecified+no_connect"))
    )
  )
)
